# litefury5-final.net
KiCad netlist of a schematic drawn in EAGLE
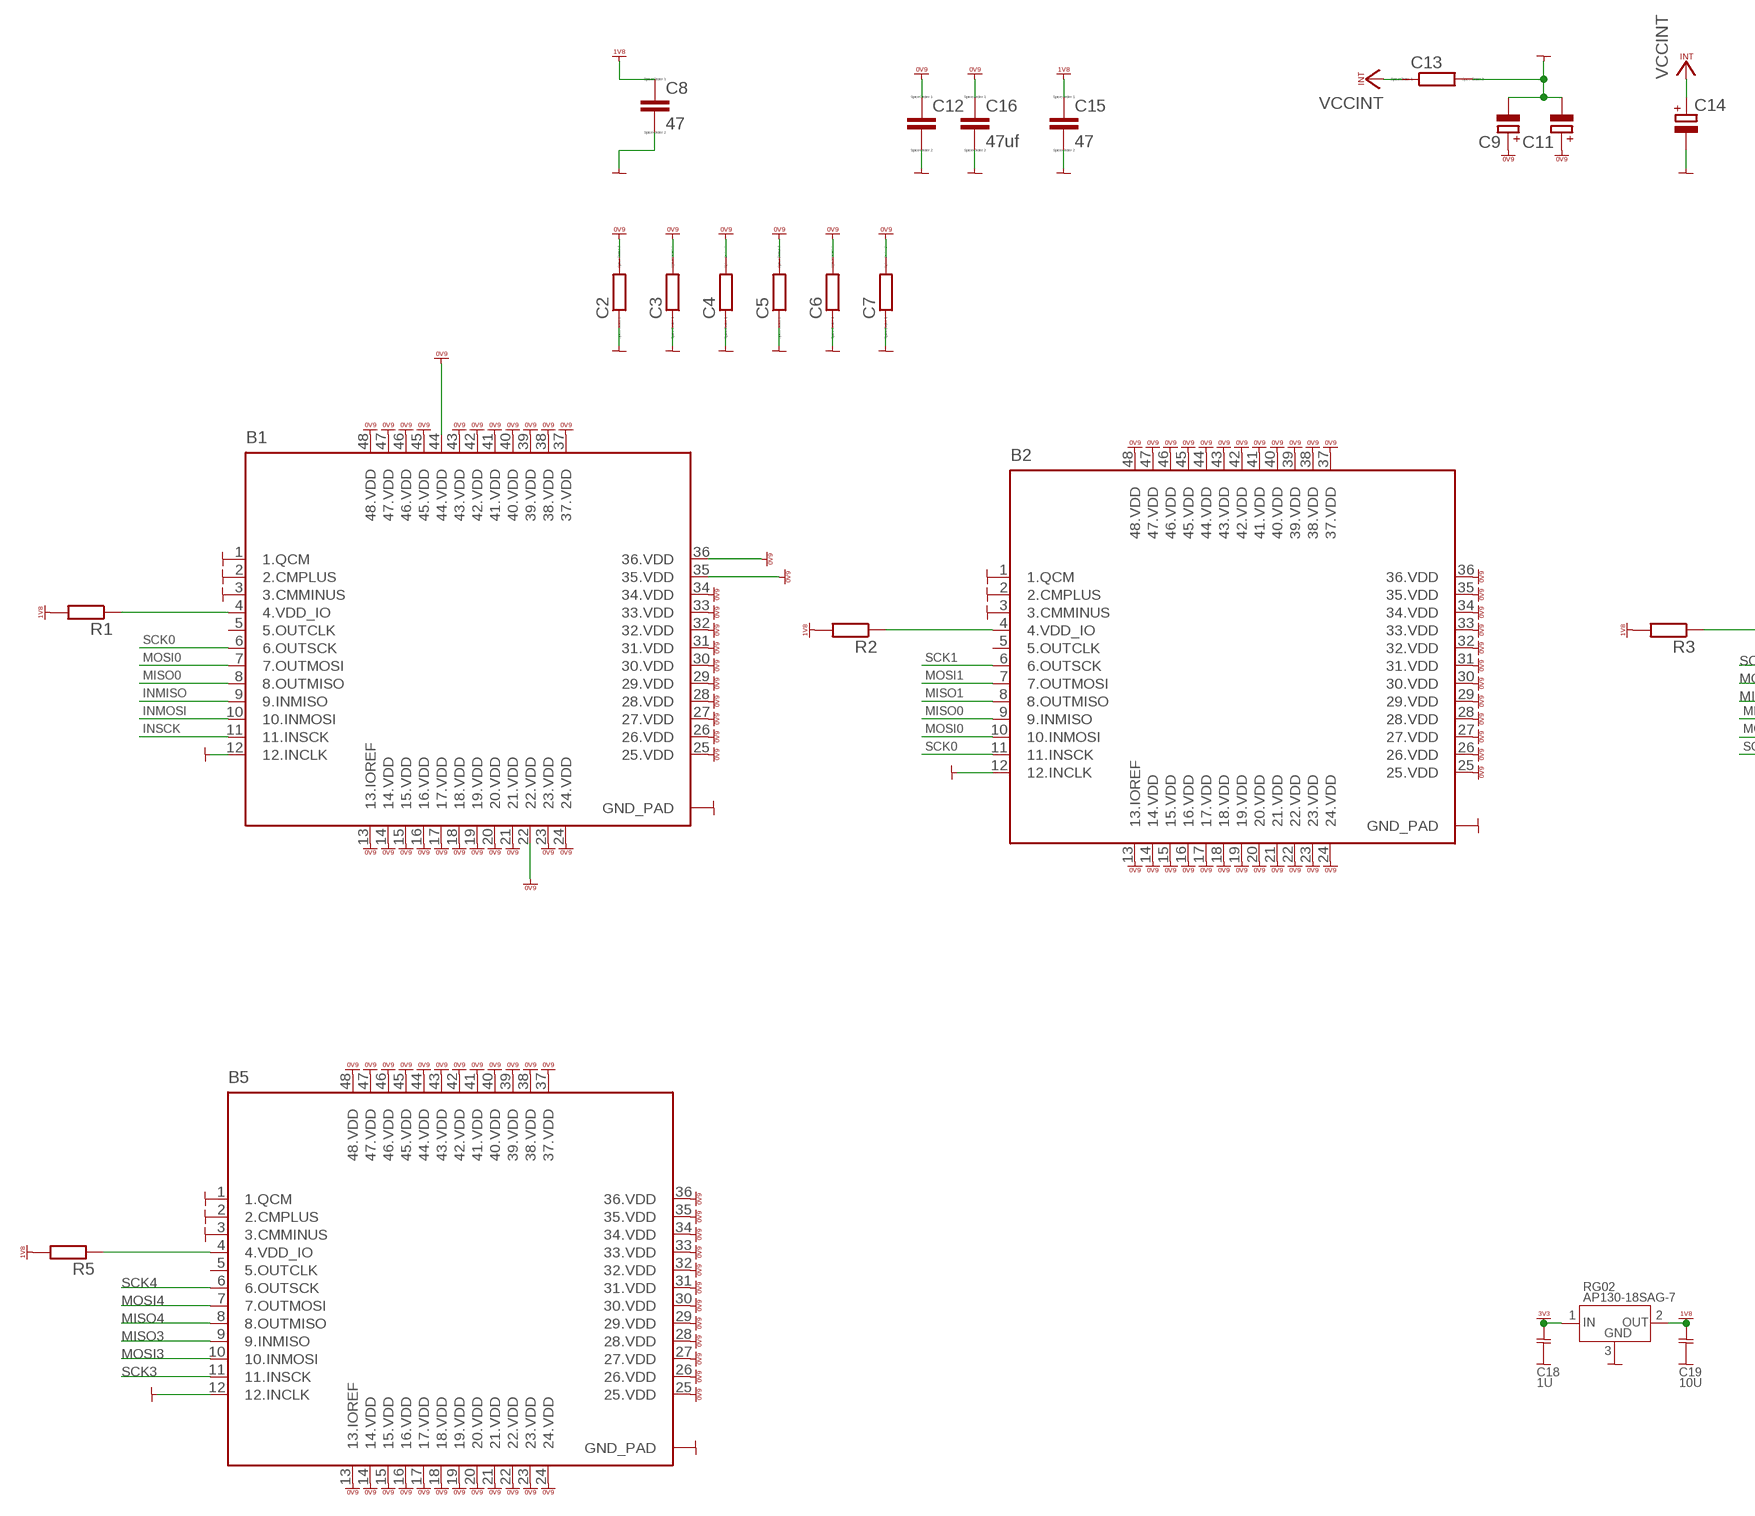
[diagram p0: schematic, sheet 1, part 1 of 2]
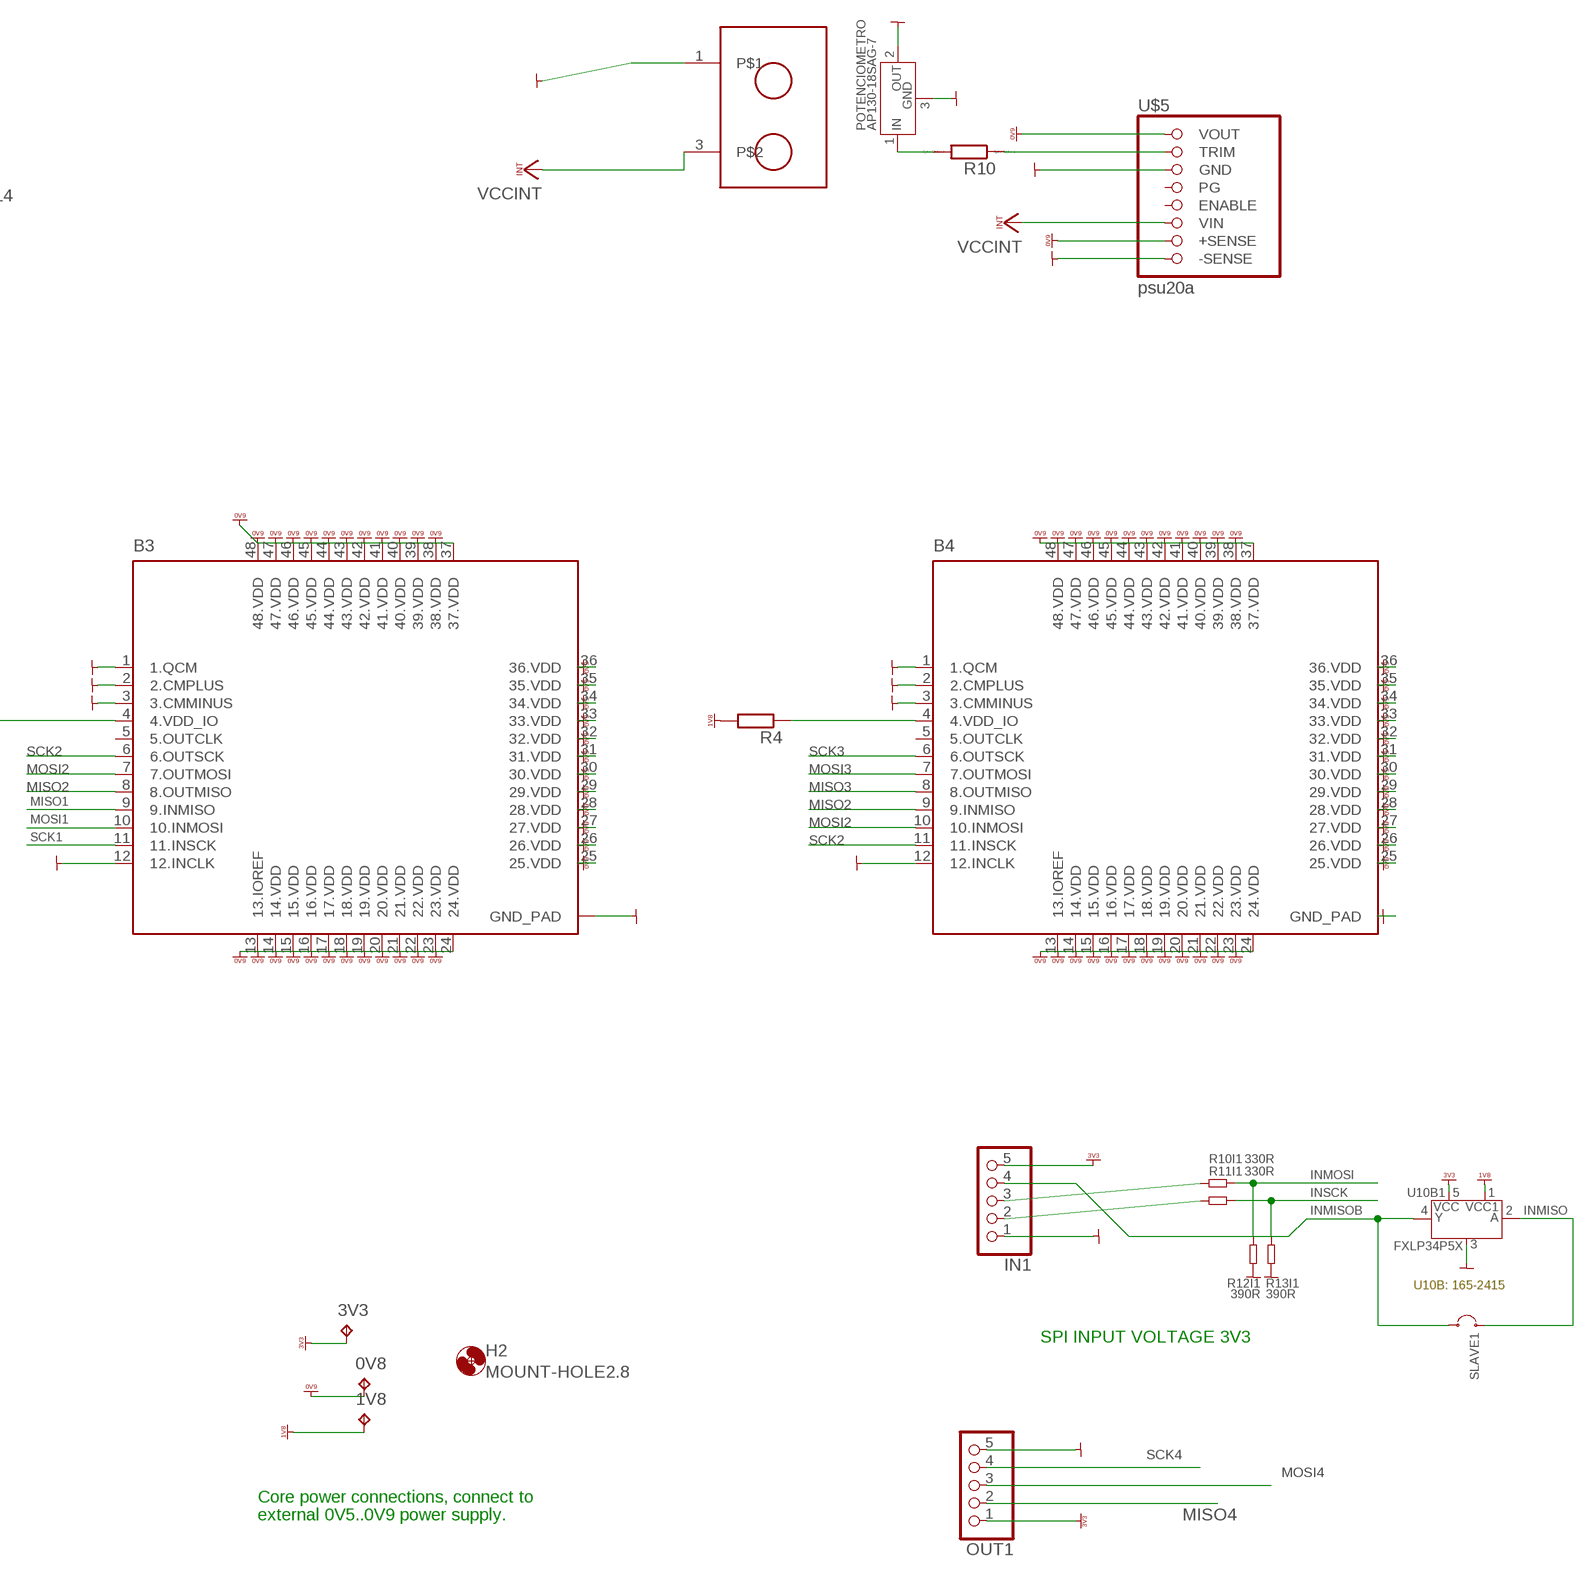
[diagram p1: schematic, sheet 1, part 2 of 2]

(export (version "E")
  (design (tool "Eeschema 10.0.6"))
  (components
    (comp (ref "0V8")
      (value "TPTP14SQ")
      (footprint "eagle-import:TP14SQ")
      (libsource (lib "eagle-import") (part "TPTP14SQ"))
    )
    (comp (ref "1V8")
      (value "TPTP10SQ")
      (footprint "eagle-import:TP10SQ")
      (libsource (lib "eagle-import") (part "TPTP10SQ"))
    )
    (comp (ref "3V3")
      (value "TPTP14SQ")
      (footprint "eagle-import:TP14SQ")
      (libsource (lib "eagle-import") (part "TPTP14SQ"))
    )
    (comp (ref "B1")
      (value "BITFURYM")
      (footprint "eagle-import:QFN48")
      (libsource (lib "eagle-import") (part "BITFURYM"))
    )
    (comp (ref "B2")
      (value "BITFURYM")
      (footprint "eagle-import:QFN48")
      (libsource (lib "eagle-import") (part "BITFURYM"))
    )
    (comp (ref "B3")
      (value "BITFURYM")
      (footprint "eagle-import:QFN48")
      (libsource (lib "eagle-import") (part "BITFURYM"))
    )
    (comp (ref "B4")
      (value "BITFURYM")
      (footprint "eagle-import:QFN48")
      (libsource (lib "eagle-import") (part "BITFURYM"))
    )
    (comp (ref "B5")
      (value "BITFURYM")
      (footprint "eagle-import:QFN48")
      (libsource (lib "eagle-import") (part "BITFURYM"))
    )
    (comp (ref "C2")
      (value "RR2010")
      (footprint "eagle-import:R2010")
      (libsource (lib "eagle-import") (part "RR2010"))
    )
    (comp (ref "C3")
      (value "RR2010")
      (footprint "eagle-import:R2010")
      (libsource (lib "eagle-import") (part "RR2010"))
    )
    (comp (ref "C4")
      (value "RR2010")
      (footprint "eagle-import:R2010")
      (libsource (lib "eagle-import") (part "RR2010"))
    )
    (comp (ref "C5")
      (value "RR2010")
      (footprint "eagle-import:R2010")
      (libsource (lib "eagle-import") (part "RR2010"))
    )
    (comp (ref "C6")
      (value "RR2010")
      (footprint "eagle-import:R2010")
      (libsource (lib "eagle-import") (part "RR2010"))
    )
    (comp (ref "C7")
      (value "RR2010")
      (footprint "eagle-import:R2010")
      (libsource (lib "eagle-import") (part "RR2010"))
    )
    (comp (ref "C8")
      (value "47")
      (footprint "eagle-import:C1210")
      (libsource (lib "eagle-import") (part "CC1210"))
    )
    (comp (ref "C9")
      (value "CPOL-EUCT7343")
      (footprint "eagle-import:CT7343")
      (libsource (lib "eagle-import") (part "CPOL-EUCT7343"))
    )
    (comp (ref "C11")
      (value "CPOL-EUCT7343")
      (footprint "eagle-import:CT7343")
      (libsource (lib "eagle-import") (part "CPOL-EUCT7343"))
    )
    (comp (ref "C12")
      (value "CC1210")
      (footprint "eagle-import:C1210")
      (libsource (lib "eagle-import") (part "CC1210"))
    )
    (comp (ref "C13")
      (value "RR2010")
      (footprint "eagle-import:R2010")
      (libsource (lib "eagle-import") (part "RR2010"))
    )
    (comp (ref "C14")
      (value "CPOL-EUCT7343")
      (footprint "eagle-import:CT7343")
      (libsource (lib "eagle-import") (part "CPOL-EUCT7343"))
    )
    (comp (ref "C15")
      (value "47")
      (footprint "eagle-import:C1210")
      (libsource (lib "eagle-import") (part "CC1210"))
    )
    (comp (ref "C16")
      (value "47uf")
      (footprint "eagle-import:C1210")
      (libsource (lib "eagle-import") (part "CC1210"))
    )
    (comp (ref "C18")
      (value "1U")
      (footprint "eagle-import:CAP0603")
      (libsource (lib "eagle-import") (part "CAP0603"))
    )
    (comp (ref "C19")
      (value "10U")
      (footprint "eagle-import:CAP0603")
      (libsource (lib "eagle-import") (part "CAP0603"))
    )
    (comp (ref "H2")
      (value "MOUNT-HOLE2.8")
      (footprint "eagle-import:2,8")
      (libsource (lib "eagle-import") (part "MOUNT-HOLE2.8"))
    )
    (comp (ref "IN1")
      (value "PINHD-1X5/90")
      (footprint "eagle-import:1X05_90")
      (libsource (lib "eagle-import") (part "PINHD-1X5/90"))
    )
    (comp (ref "OUT1")
      (value "PINHD-1X5/90")
      (footprint "eagle-import:1X05_90")
      (libsource (lib "eagle-import") (part "PINHD-1X5/90"))
    )
    (comp (ref "POTENCIOMETRO")
      (value "AP130-18SAG-7")
      (footprint "eagle-import:SOT23")
      (libsource (lib "eagle-import") (part "AP130-18SAG-7"))
    )
    (comp (ref "R1")
      (value "R-EU_R1206")
      (footprint "eagle-import:R1206")
      (libsource (lib "eagle-import") (part "R-EU_R1206"))
    )
    (comp (ref "R2")
      (value "R-EU_R1206")
      (footprint "eagle-import:R1206")
      (libsource (lib "eagle-import") (part "R-EU_R1206"))
    )
    (comp (ref "R3")
      (value "R-EU_R1206")
      (footprint "eagle-import:R1206")
      (libsource (lib "eagle-import") (part "R-EU_R1206"))
    )
    (comp (ref "R4")
      (value "R-EU_R1206")
      (footprint "eagle-import:R1206")
      (libsource (lib "eagle-import") (part "R-EU_R1206"))
    )
    (comp (ref "R5")
      (value "R-EU_R1206")
      (footprint "eagle-import:R1206")
      (libsource (lib "eagle-import") (part "R-EU_R1206"))
    )
    (comp (ref "R10")
      (value "RR0603")
      (footprint "eagle-import:R0603")
      (libsource (lib "eagle-import") (part "RR0603"))
    )
    (comp (ref "R10I1")
      (value "330R")
      (footprint "eagle-import:RES0603")
      (libsource (lib "eagle-import") (part "RES0603"))
    )
    (comp (ref "R11I1")
      (value "330R")
      (footprint "eagle-import:RES0603")
      (libsource (lib "eagle-import") (part "RES0603"))
    )
    (comp (ref "R12I1")
      (value "390R")
      (footprint "eagle-import:RES0603")
      (libsource (lib "eagle-import") (part "RES0603"))
    )
    (comp (ref "R13I1")
      (value "390R")
      (footprint "eagle-import:RES0603")
      (libsource (lib "eagle-import") (part "RES0603"))
    )
    (comp (ref "RG02")
      (value "AP130-18SAG-7")
      (footprint "eagle-import:SOT23")
      (libsource (lib "eagle-import") (part "AP130-18SAG-7"))
    )
    (comp (ref "SLAVE1")
      (value "SJ2SJ2-S")
      (footprint "eagle-import:SJ2-S")
      (libsource (lib "eagle-import") (part "SJ2SJ2-S"))
    )
    (comp (ref "U$5")
      (value "D12S05020")
      (footprint "eagle-import:PSU20A")
      (libsource (lib "eagle-import") (part "D12S05020"))
    )
    (comp (ref "U$6")
      (value "RTORNILLO")
      (footprint "eagle-import:REGLETATORNILLO")
      (libsource (lib "eagle-import") (part "RTORNILLO"))
    )
    (comp (ref "U10B1")
      (value "FXLP34P5X")
      (footprint "eagle-import:SOT23-5")
      (libsource (lib "eagle-import") (part "FXLP34P5X"))
    )
  )
  (nets
    (net (code "1") (name "/INMISO") (class "Default")
      (node (ref "B1") (pin "9") (pinfunction "9.INMISO_9") (pintype "bidirectional"))
      (node (ref "SLAVE1") (pin "2") (pinfunction "P$2_2") (pintype "passive"))
      (node (ref "U10B1") (pin "2") (pinfunction "2.A_2") (pintype "passive"))
    )
    (net (code "2") (name "/INMISOB") (class "Default")
      (node (ref "IN1") (pin "4") (pinfunction "4_4") (pintype "passive"))
      (node (ref "SLAVE1") (pin "1") (pinfunction "P$1_1") (pintype "passive"))
      (node (ref "U10B1") (pin "4") (pinfunction "4.Y_4") (pintype "passive"))
    )
    (net (code "3") (name "/INMOSI") (class "Default")
      (node (ref "B1") (pin "10") (pinfunction "10.INMOSI_10") (pintype "bidirectional"))
      (node (ref "R10I1") (pin "2") (pinfunction "2_2") (pintype "passive"))
      (node (ref "R12I1") (pin "2") (pinfunction "2_2") (pintype "passive"))
    )
    (net (code "4") (name "/INSCK") (class "Default")
      (node (ref "B1") (pin "11") (pinfunction "11.INSCK_11") (pintype "bidirectional"))
      (node (ref "R11I1") (pin "2") (pinfunction "2_2") (pintype "passive"))
      (node (ref "R13I1") (pin "2") (pinfunction "2_2") (pintype "passive"))
    )
    (net (code "5") (name "/MISO0") (class "Default")
      (node (ref "B1") (pin "8") (pinfunction "8.OUTMISO_8") (pintype "bidirectional"))
      (node (ref "B2") (pin "9") (pinfunction "9.INMISO_9") (pintype "bidirectional"))
    )
    (net (code "6") (name "/MISO1") (class "Default")
      (node (ref "B2") (pin "8") (pinfunction "8.OUTMISO_8") (pintype "bidirectional"))
      (node (ref "B3") (pin "9") (pinfunction "9.INMISO_9") (pintype "bidirectional"))
    )
    (net (code "7") (name "/MISO2") (class "Default")
      (node (ref "B3") (pin "8") (pinfunction "8.OUTMISO_8") (pintype "bidirectional"))
      (node (ref "B4") (pin "9") (pinfunction "9.INMISO_9") (pintype "bidirectional"))
    )
    (net (code "8") (name "/MISO3") (class "Default")
      (node (ref "B4") (pin "8") (pinfunction "8.OUTMISO_8") (pintype "bidirectional"))
      (node (ref "B5") (pin "9") (pinfunction "9.INMISO_9") (pintype "bidirectional"))
    )
    (net (code "9") (name "/MISO4") (class "Default")
      (node (ref "B5") (pin "8") (pinfunction "8.OUTMISO_8") (pintype "bidirectional"))
      (node (ref "OUT1") (pin "2") (pinfunction "2_2") (pintype "passive"))
    )
    (net (code "10") (name "/MOSI0") (class "Default")
      (node (ref "B1") (pin "7") (pinfunction "7.OUTMOSI_7") (pintype "bidirectional"))
      (node (ref "B2") (pin "10") (pinfunction "10.INMOSI_10") (pintype "bidirectional"))
    )
    (net (code "11") (name "/MOSI1") (class "Default")
      (node (ref "B2") (pin "7") (pinfunction "7.OUTMOSI_7") (pintype "bidirectional"))
      (node (ref "B3") (pin "10") (pinfunction "10.INMOSI_10") (pintype "bidirectional"))
    )
    (net (code "12") (name "/MOSI2") (class "Default")
      (node (ref "B3") (pin "7") (pinfunction "7.OUTMOSI_7") (pintype "bidirectional"))
      (node (ref "B4") (pin "10") (pinfunction "10.INMOSI_10") (pintype "bidirectional"))
    )
    (net (code "13") (name "/MOSI3") (class "Default")
      (node (ref "B4") (pin "7") (pinfunction "7.OUTMOSI_7") (pintype "bidirectional"))
      (node (ref "B5") (pin "10") (pinfunction "10.INMOSI_10") (pintype "bidirectional"))
    )
    (net (code "14") (name "/MOSI4") (class "Default")
      (node (ref "B5") (pin "7") (pinfunction "7.OUTMOSI_7") (pintype "bidirectional"))
      (node (ref "OUT1") (pin "3") (pinfunction "3_3") (pintype "passive"))
    )
    (net (code "15") (name "/SCK0") (class "Default")
      (node (ref "B1") (pin "6") (pinfunction "6.OUTSCK_6") (pintype "bidirectional"))
      (node (ref "B2") (pin "11") (pinfunction "11.INSCK_11") (pintype "bidirectional"))
    )
    (net (code "16") (name "/SCK1") (class "Default")
      (node (ref "B2") (pin "6") (pinfunction "6.OUTSCK_6") (pintype "bidirectional"))
      (node (ref "B3") (pin "11") (pinfunction "11.INSCK_11") (pintype "bidirectional"))
    )
    (net (code "17") (name "/SCK2") (class "Default")
      (node (ref "B3") (pin "6") (pinfunction "6.OUTSCK_6") (pintype "bidirectional"))
      (node (ref "B4") (pin "11") (pinfunction "11.INSCK_11") (pintype "bidirectional"))
    )
    (net (code "18") (name "/SCK3") (class "Default")
      (node (ref "B4") (pin "6") (pinfunction "6.OUTSCK_6") (pintype "bidirectional"))
      (node (ref "B5") (pin "11") (pinfunction "11.INSCK_11") (pintype "bidirectional"))
    )
    (net (code "19") (name "/SCK4") (class "Default")
      (node (ref "B5") (pin "6") (pinfunction "6.OUTSCK_6") (pintype "bidirectional"))
      (node (ref "OUT1") (pin "4") (pinfunction "4_4") (pintype "passive"))
    )
    (net (code "20") (name "GND") (class "Default")
      (node (ref "B1") (pin "1") (pinfunction "1.QCM_1") (pintype "bidirectional"))
      (node (ref "B1") (pin "12") (pinfunction "12.INCLK_12") (pintype "bidirectional"))
      (node (ref "B1") (pin "2") (pinfunction "2.CMPLUS_2") (pintype "bidirectional"))
      (node (ref "B1") (pin "3") (pinfunction "3.CMMINUS_3") (pintype "bidirectional"))
      (node (ref "B1") (pin "EXP") (pinfunction "GND_PAD_EXP") (pintype "bidirectional"))
      (node (ref "B1") (pin "P$1") (pinfunction "GND_PAD_P$1") (pintype "bidirectional"))
      (node (ref "B1") (pin "P$10") (pinfunction "GND_PAD_P$10") (pintype "bidirectional"))
      (node (ref "B1") (pin "P$11") (pinfunction "GND_PAD_P$11") (pintype "bidirectional"))
      (node (ref "B1") (pin "P$12") (pinfunction "GND_PAD_P$12") (pintype "bidirectional"))
      (node (ref "B1") (pin "P$13") (pinfunction "GND_PAD_P$13") (pintype "bidirectional"))
      (node (ref "B1") (pin "P$14") (pinfunction "GND_PAD_P$14") (pintype "bidirectional"))
      (node (ref "B1") (pin "P$15") (pinfunction "GND_PAD_P$15") (pintype "bidirectional"))
      (node (ref "B1") (pin "P$16") (pinfunction "GND_PAD_P$16") (pintype "bidirectional"))
      (node (ref "B1") (pin "P$17") (pinfunction "GND_PAD_P$17") (pintype "bidirectional"))
      (node (ref "B1") (pin "P$18") (pinfunction "GND_PAD_P$18") (pintype "bidirectional"))
      (node (ref "B1") (pin "P$19") (pinfunction "GND_PAD_P$19") (pintype "bidirectional"))
      (node (ref "B1") (pin "P$2") (pinfunction "GND_PAD_P$2") (pintype "bidirectional"))
      (node (ref "B1") (pin "P$20") (pinfunction "GND_PAD_P$20") (pintype "bidirectional"))
      (node (ref "B1") (pin "P$21") (pinfunction "GND_PAD_P$21") (pintype "bidirectional"))
      (node (ref "B1") (pin "P$22") (pinfunction "GND_PAD_P$22") (pintype "bidirectional"))
      (node (ref "B1") (pin "P$23") (pinfunction "GND_PAD_P$23") (pintype "bidirectional"))
      (node (ref "B1") (pin "P$24") (pinfunction "GND_PAD_P$24") (pintype "bidirectional"))
      (node (ref "B1") (pin "P$25") (pinfunction "GND_PAD_P$25") (pintype "bidirectional"))
      (node (ref "B1") (pin "P$3") (pinfunction "GND_PAD_P$3") (pintype "bidirectional"))
      (node (ref "B1") (pin "P$4") (pinfunction "GND_PAD_P$4") (pintype "bidirectional"))
      (node (ref "B1") (pin "P$5") (pinfunction "GND_PAD_P$5") (pintype "bidirectional"))
      (node (ref "B1") (pin "P$6") (pinfunction "GND_PAD_P$6") (pintype "bidirectional"))
      (node (ref "B1") (pin "P$7") (pinfunction "GND_PAD_P$7") (pintype "bidirectional"))
      (node (ref "B1") (pin "P$8") (pinfunction "GND_PAD_P$8") (pintype "bidirectional"))
      (node (ref "B1") (pin "P$9") (pinfunction "GND_PAD_P$9") (pintype "bidirectional"))
      (node (ref "B2") (pin "1") (pinfunction "1.QCM_1") (pintype "bidirectional"))
      (node (ref "B2") (pin "12") (pinfunction "12.INCLK_12") (pintype "bidirectional"))
      (node (ref "B2") (pin "2") (pinfunction "2.CMPLUS_2") (pintype "bidirectional"))
      (node (ref "B2") (pin "3") (pinfunction "3.CMMINUS_3") (pintype "bidirectional"))
      (node (ref "B2") (pin "EXP") (pinfunction "GND_PAD_EXP") (pintype "bidirectional"))
      (node (ref "B2") (pin "P$1") (pinfunction "GND_PAD_P$1") (pintype "bidirectional"))
      (node (ref "B2") (pin "P$10") (pinfunction "GND_PAD_P$10") (pintype "bidirectional"))
      (node (ref "B2") (pin "P$11") (pinfunction "GND_PAD_P$11") (pintype "bidirectional"))
      (node (ref "B2") (pin "P$12") (pinfunction "GND_PAD_P$12") (pintype "bidirectional"))
      (node (ref "B2") (pin "P$13") (pinfunction "GND_PAD_P$13") (pintype "bidirectional"))
      (node (ref "B2") (pin "P$14") (pinfunction "GND_PAD_P$14") (pintype "bidirectional"))
      (node (ref "B2") (pin "P$15") (pinfunction "GND_PAD_P$15") (pintype "bidirectional"))
      (node (ref "B2") (pin "P$16") (pinfunction "GND_PAD_P$16") (pintype "bidirectional"))
      (node (ref "B2") (pin "P$17") (pinfunction "GND_PAD_P$17") (pintype "bidirectional"))
      (node (ref "B2") (pin "P$18") (pinfunction "GND_PAD_P$18") (pintype "bidirectional"))
      (node (ref "B2") (pin "P$19") (pinfunction "GND_PAD_P$19") (pintype "bidirectional"))
      (node (ref "B2") (pin "P$2") (pinfunction "GND_PAD_P$2") (pintype "bidirectional"))
      (node (ref "B2") (pin "P$20") (pinfunction "GND_PAD_P$20") (pintype "bidirectional"))
      (node (ref "B2") (pin "P$21") (pinfunction "GND_PAD_P$21") (pintype "bidirectional"))
      (node (ref "B2") (pin "P$22") (pinfunction "GND_PAD_P$22") (pintype "bidirectional"))
      (node (ref "B2") (pin "P$23") (pinfunction "GND_PAD_P$23") (pintype "bidirectional"))
      (node (ref "B2") (pin "P$24") (pinfunction "GND_PAD_P$24") (pintype "bidirectional"))
      (node (ref "B2") (pin "P$25") (pinfunction "GND_PAD_P$25") (pintype "bidirectional"))
      (node (ref "B2") (pin "P$3") (pinfunction "GND_PAD_P$3") (pintype "bidirectional"))
      (node (ref "B2") (pin "P$4") (pinfunction "GND_PAD_P$4") (pintype "bidirectional"))
      (node (ref "B2") (pin "P$5") (pinfunction "GND_PAD_P$5") (pintype "bidirectional"))
      (node (ref "B2") (pin "P$6") (pinfunction "GND_PAD_P$6") (pintype "bidirectional"))
      (node (ref "B2") (pin "P$7") (pinfunction "GND_PAD_P$7") (pintype "bidirectional"))
      (node (ref "B2") (pin "P$8") (pinfunction "GND_PAD_P$8") (pintype "bidirectional"))
      (node (ref "B2") (pin "P$9") (pinfunction "GND_PAD_P$9") (pintype "bidirectional"))
      (node (ref "B3") (pin "1") (pinfunction "1.QCM_1") (pintype "bidirectional"))
      (node (ref "B3") (pin "12") (pinfunction "12.INCLK_12") (pintype "bidirectional"))
      (node (ref "B3") (pin "2") (pinfunction "2.CMPLUS_2") (pintype "bidirectional"))
      (node (ref "B3") (pin "3") (pinfunction "3.CMMINUS_3") (pintype "bidirectional"))
      (node (ref "B3") (pin "EXP") (pinfunction "GND_PAD_EXP") (pintype "bidirectional"))
      (node (ref "B3") (pin "P$1") (pinfunction "GND_PAD_P$1") (pintype "bidirectional"))
      (node (ref "B3") (pin "P$10") (pinfunction "GND_PAD_P$10") (pintype "bidirectional"))
      (node (ref "B3") (pin "P$11") (pinfunction "GND_PAD_P$11") (pintype "bidirectional"))
      (node (ref "B3") (pin "P$12") (pinfunction "GND_PAD_P$12") (pintype "bidirectional"))
      (node (ref "B3") (pin "P$13") (pinfunction "GND_PAD_P$13") (pintype "bidirectional"))
      (node (ref "B3") (pin "P$14") (pinfunction "GND_PAD_P$14") (pintype "bidirectional"))
      (node (ref "B3") (pin "P$15") (pinfunction "GND_PAD_P$15") (pintype "bidirectional"))
      (node (ref "B3") (pin "P$16") (pinfunction "GND_PAD_P$16") (pintype "bidirectional"))
      (node (ref "B3") (pin "P$17") (pinfunction "GND_PAD_P$17") (pintype "bidirectional"))
      (node (ref "B3") (pin "P$18") (pinfunction "GND_PAD_P$18") (pintype "bidirectional"))
      (node (ref "B3") (pin "P$19") (pinfunction "GND_PAD_P$19") (pintype "bidirectional"))
      (node (ref "B3") (pin "P$2") (pinfunction "GND_PAD_P$2") (pintype "bidirectional"))
      (node (ref "B3") (pin "P$20") (pinfunction "GND_PAD_P$20") (pintype "bidirectional"))
      (node (ref "B3") (pin "P$21") (pinfunction "GND_PAD_P$21") (pintype "bidirectional"))
      (node (ref "B3") (pin "P$22") (pinfunction "GND_PAD_P$22") (pintype "bidirectional"))
      (node (ref "B3") (pin "P$23") (pinfunction "GND_PAD_P$23") (pintype "bidirectional"))
      (node (ref "B3") (pin "P$24") (pinfunction "GND_PAD_P$24") (pintype "bidirectional"))
      (node (ref "B3") (pin "P$25") (pinfunction "GND_PAD_P$25") (pintype "bidirectional"))
      (node (ref "B3") (pin "P$3") (pinfunction "GND_PAD_P$3") (pintype "bidirectional"))
      (node (ref "B3") (pin "P$4") (pinfunction "GND_PAD_P$4") (pintype "bidirectional"))
      (node (ref "B3") (pin "P$5") (pinfunction "GND_PAD_P$5") (pintype "bidirectional"))
      (node (ref "B3") (pin "P$6") (pinfunction "GND_PAD_P$6") (pintype "bidirectional"))
      (node (ref "B3") (pin "P$7") (pinfunction "GND_PAD_P$7") (pintype "bidirectional"))
      (node (ref "B3") (pin "P$8") (pinfunction "GND_PAD_P$8") (pintype "bidirectional"))
      (node (ref "B3") (pin "P$9") (pinfunction "GND_PAD_P$9") (pintype "bidirectional"))
      (node (ref "B4") (pin "1") (pinfunction "1.QCM_1") (pintype "bidirectional"))
      (node (ref "B4") (pin "12") (pinfunction "12.INCLK_12") (pintype "bidirectional"))
      (node (ref "B4") (pin "2") (pinfunction "2.CMPLUS_2") (pintype "bidirectional"))
      (node (ref "B4") (pin "3") (pinfunction "3.CMMINUS_3") (pintype "bidirectional"))
      (node (ref "B4") (pin "EXP") (pinfunction "GND_PAD_EXP") (pintype "bidirectional"))
      (node (ref "B4") (pin "P$1") (pinfunction "GND_PAD_P$1") (pintype "bidirectional"))
      (node (ref "B4") (pin "P$10") (pinfunction "GND_PAD_P$10") (pintype "bidirectional"))
      (node (ref "B4") (pin "P$11") (pinfunction "GND_PAD_P$11") (pintype "bidirectional"))
      (node (ref "B4") (pin "P$12") (pinfunction "GND_PAD_P$12") (pintype "bidirectional"))
      (node (ref "B4") (pin "P$13") (pinfunction "GND_PAD_P$13") (pintype "bidirectional"))
      (node (ref "B4") (pin "P$14") (pinfunction "GND_PAD_P$14") (pintype "bidirectional"))
      (node (ref "B4") (pin "P$15") (pinfunction "GND_PAD_P$15") (pintype "bidirectional"))
      (node (ref "B4") (pin "P$16") (pinfunction "GND_PAD_P$16") (pintype "bidirectional"))
      (node (ref "B4") (pin "P$17") (pinfunction "GND_PAD_P$17") (pintype "bidirectional"))
      (node (ref "B4") (pin "P$18") (pinfunction "GND_PAD_P$18") (pintype "bidirectional"))
      (node (ref "B4") (pin "P$19") (pinfunction "GND_PAD_P$19") (pintype "bidirectional"))
      (node (ref "B4") (pin "P$2") (pinfunction "GND_PAD_P$2") (pintype "bidirectional"))
      (node (ref "B4") (pin "P$20") (pinfunction "GND_PAD_P$20") (pintype "bidirectional"))
      (node (ref "B4") (pin "P$21") (pinfunction "GND_PAD_P$21") (pintype "bidirectional"))
      (node (ref "B4") (pin "P$22") (pinfunction "GND_PAD_P$22") (pintype "bidirectional"))
      (node (ref "B4") (pin "P$23") (pinfunction "GND_PAD_P$23") (pintype "bidirectional"))
      (node (ref "B4") (pin "P$24") (pinfunction "GND_PAD_P$24") (pintype "bidirectional"))
      (node (ref "B4") (pin "P$25") (pinfunction "GND_PAD_P$25") (pintype "bidirectional"))
      (node (ref "B4") (pin "P$3") (pinfunction "GND_PAD_P$3") (pintype "bidirectional"))
      (node (ref "B4") (pin "P$4") (pinfunction "GND_PAD_P$4") (pintype "bidirectional"))
      (node (ref "B4") (pin "P$5") (pinfunction "GND_PAD_P$5") (pintype "bidirectional"))
      (node (ref "B4") (pin "P$6") (pinfunction "GND_PAD_P$6") (pintype "bidirectional"))
      (node (ref "B4") (pin "P$7") (pinfunction "GND_PAD_P$7") (pintype "bidirectional"))
      (node (ref "B4") (pin "P$8") (pinfunction "GND_PAD_P$8") (pintype "bidirectional"))
      (node (ref "B4") (pin "P$9") (pinfunction "GND_PAD_P$9") (pintype "bidirectional"))
      (node (ref "B5") (pin "1") (pinfunction "1.QCM_1") (pintype "bidirectional"))
      (node (ref "B5") (pin "12") (pinfunction "12.INCLK_12") (pintype "bidirectional"))
      (node (ref "B5") (pin "2") (pinfunction "2.CMPLUS_2") (pintype "bidirectional"))
      (node (ref "B5") (pin "3") (pinfunction "3.CMMINUS_3") (pintype "bidirectional"))
      (node (ref "B5") (pin "EXP") (pinfunction "GND_PAD_EXP") (pintype "bidirectional"))
      (node (ref "B5") (pin "P$1") (pinfunction "GND_PAD_P$1") (pintype "bidirectional"))
      (node (ref "B5") (pin "P$10") (pinfunction "GND_PAD_P$10") (pintype "bidirectional"))
      (node (ref "B5") (pin "P$11") (pinfunction "GND_PAD_P$11") (pintype "bidirectional"))
      (node (ref "B5") (pin "P$12") (pinfunction "GND_PAD_P$12") (pintype "bidirectional"))
      (node (ref "B5") (pin "P$13") (pinfunction "GND_PAD_P$13") (pintype "bidirectional"))
      (node (ref "B5") (pin "P$14") (pinfunction "GND_PAD_P$14") (pintype "bidirectional"))
      (node (ref "B5") (pin "P$15") (pinfunction "GND_PAD_P$15") (pintype "bidirectional"))
      (node (ref "B5") (pin "P$16") (pinfunction "GND_PAD_P$16") (pintype "bidirectional"))
      (node (ref "B5") (pin "P$17") (pinfunction "GND_PAD_P$17") (pintype "bidirectional"))
      (node (ref "B5") (pin "P$18") (pinfunction "GND_PAD_P$18") (pintype "bidirectional"))
      (node (ref "B5") (pin "P$19") (pinfunction "GND_PAD_P$19") (pintype "bidirectional"))
      (node (ref "B5") (pin "P$2") (pinfunction "GND_PAD_P$2") (pintype "bidirectional"))
      (node (ref "B5") (pin "P$20") (pinfunction "GND_PAD_P$20") (pintype "bidirectional"))
      (node (ref "B5") (pin "P$21") (pinfunction "GND_PAD_P$21") (pintype "bidirectional"))
      (node (ref "B5") (pin "P$22") (pinfunction "GND_PAD_P$22") (pintype "bidirectional"))
      (node (ref "B5") (pin "P$23") (pinfunction "GND_PAD_P$23") (pintype "bidirectional"))
      (node (ref "B5") (pin "P$24") (pinfunction "GND_PAD_P$24") (pintype "bidirectional"))
      (node (ref "B5") (pin "P$25") (pinfunction "GND_PAD_P$25") (pintype "bidirectional"))
      (node (ref "B5") (pin "P$3") (pinfunction "GND_PAD_P$3") (pintype "bidirectional"))
      (node (ref "B5") (pin "P$4") (pinfunction "GND_PAD_P$4") (pintype "bidirectional"))
      (node (ref "B5") (pin "P$5") (pinfunction "GND_PAD_P$5") (pintype "bidirectional"))
      (node (ref "B5") (pin "P$6") (pinfunction "GND_PAD_P$6") (pintype "bidirectional"))
      (node (ref "B5") (pin "P$7") (pinfunction "GND_PAD_P$7") (pintype "bidirectional"))
      (node (ref "B5") (pin "P$8") (pinfunction "GND_PAD_P$8") (pintype "bidirectional"))
      (node (ref "B5") (pin "P$9") (pinfunction "GND_PAD_P$9") (pintype "bidirectional"))
      (node (ref "C11") (pin "-") (pinfunction "-_-") (pintype "passive"))
      (node (ref "C12") (pin "2") (pinfunction "2_2") (pintype "passive"))
      (node (ref "C13") (pin "2") (pinfunction "2_2") (pintype "passive"))
      (node (ref "C14") (pin "-") (pinfunction "-_-") (pintype "passive"))
      (node (ref "C15") (pin "2") (pinfunction "2_2") (pintype "passive"))
      (node (ref "C16") (pin "2") (pinfunction "2_2") (pintype "passive"))
      (node (ref "C18") (pin "2") (pinfunction "2_2") (pintype "passive"))
      (node (ref "C19") (pin "2") (pinfunction "2_2") (pintype "passive"))
      (node (ref "C2") (pin "1") (pinfunction "1_1") (pintype "passive"))
      (node (ref "C3") (pin "1") (pinfunction "1_1") (pintype "passive"))
      (node (ref "C4") (pin "1") (pinfunction "1_1") (pintype "passive"))
      (node (ref "C5") (pin "1") (pinfunction "1_1") (pintype "passive"))
      (node (ref "C6") (pin "1") (pinfunction "1_1") (pintype "passive"))
      (node (ref "C7") (pin "1") (pinfunction "1_1") (pintype "passive"))
      (node (ref "C8") (pin "2") (pinfunction "2_2") (pintype "passive"))
      (node (ref "C9") (pin "-") (pinfunction "-_-") (pintype "passive"))
      (node (ref "IN1") (pin "1") (pinfunction "1_1") (pintype "passive"))
      (node (ref "OUT1") (pin "5") (pinfunction "5_5") (pintype "passive"))
      (node (ref "POTENCIOMETRO") (pin "2") (pinfunction "2.OUT_2") (pintype "passive"))
      (node (ref "POTENCIOMETRO") (pin "3") (pinfunction "3.GND_3") (pintype "passive"))
      (node (ref "R12I1") (pin "1") (pinfunction "1_1") (pintype "passive"))
      (node (ref "R13I1") (pin "1") (pinfunction "1_1") (pintype "passive"))
      (node (ref "RG02") (pin "3") (pinfunction "3.GND_3") (pintype "passive"))
      (node (ref "U$5") (pin "3") (pinfunction "GND_3") (pintype "passive"))
      (node (ref "U$5") (pin "8") (pinfunction "-SENSE_8") (pintype "passive"))
      (node (ref "U$6") (pin "1") (pinfunction "P$1_1") (pintype "bidirectional"))
      (node (ref "U10B1") (pin "3") (pinfunction "3.GND_3") (pintype "passive"))
    )
    (net (code "21") (name "Net-(B1-4.VDD_IO)") (class "Default")
      (node (ref "B1") (pin "4") (pinfunction "4.VDD_IO_4") (pintype "bidirectional"))
      (node (ref "R1") (pin "1") (pinfunction "1_1") (pintype "passive"))
    )
    (net (code "22") (name "Net-(B2-4.VDD_IO)") (class "Default")
      (node (ref "B2") (pin "4") (pinfunction "4.VDD_IO_4") (pintype "bidirectional"))
      (node (ref "R2") (pin "1") (pinfunction "1_1") (pintype "passive"))
    )
    (net (code "23") (name "Net-(B3-4.VDD_IO)") (class "Default")
      (node (ref "B3") (pin "4") (pinfunction "4.VDD_IO_4") (pintype "bidirectional"))
      (node (ref "R3") (pin "1") (pinfunction "1_1") (pintype "passive"))
    )
    (net (code "24") (name "Net-(B4-4.VDD_IO)") (class "Default")
      (node (ref "B4") (pin "4") (pinfunction "4.VDD_IO_4") (pintype "bidirectional"))
      (node (ref "R4") (pin "1") (pinfunction "1_1") (pintype "passive"))
    )
    (net (code "25") (name "Net-(B5-4.VDD_IO)") (class "Default")
      (node (ref "B5") (pin "4") (pinfunction "4.VDD_IO_4") (pintype "bidirectional"))
      (node (ref "R5") (pin "1") (pinfunction "1_1") (pintype "passive"))
    )
    (net (code "26") (name "Net-(IN1-Pad2)") (class "Default")
      (node (ref "IN1") (pin "2") (pinfunction "2_2") (pintype "passive"))
      (node (ref "R11I1") (pin "1") (pinfunction "1_1") (pintype "passive"))
    )
    (net (code "27") (name "Net-(IN1-Pad3)") (class "Default")
      (node (ref "IN1") (pin "3") (pinfunction "3_3") (pintype "passive"))
      (node (ref "R10I1") (pin "1") (pinfunction "1_1") (pintype "passive"))
    )
    (net (code "28") (name "Net-(POTENCIOMETRO-1.IN)") (class "Default")
      (node (ref "POTENCIOMETRO") (pin "1") (pinfunction "1.IN_1") (pintype "passive"))
      (node (ref "R10") (pin "2") (pinfunction "2_2") (pintype "passive"))
    )
    (net (code "29") (name "Net-(U$5-TRIM)") (class "Default")
      (node (ref "R10") (pin "1") (pinfunction "1_1") (pintype "passive"))
      (node (ref "U$5") (pin "2") (pinfunction "TRIM_2") (pintype "passive"))
    )
    (net (code "30") (name "VCCINT") (class "Default")
      (node (ref "C13") (pin "1") (pinfunction "1_1") (pintype "passive"))
      (node (ref "C14") (pin "+") (pinfunction "+_+") (pintype "passive"))
      (node (ref "U$5") (pin "6") (pinfunction "VIN_6") (pintype "passive"))
      (node (ref "U$6") (pin "3") (pinfunction "P$2_3") (pintype "bidirectional"))
    )
    (net (code "31") (name "VCC_0V9") (class "Default")
      (node (ref "0V8") (pin "TP") (pinfunction "TP_TP") (pintype "input"))
      (node (ref "B1") (pin "13") (pinfunction "13.IOREF_13") (pintype "bidirectional"))
      (node (ref "B1") (pin "14") (pinfunction "14.VDD_14") (pintype "bidirectional"))
      (node (ref "B1") (pin "15") (pinfunction "15.VDD_15") (pintype "bidirectional"))
      (node (ref "B1") (pin "16") (pinfunction "16.VDD_16") (pintype "bidirectional"))
      (node (ref "B1") (pin "17") (pinfunction "17.VDD_17") (pintype "power_in"))
      (node (ref "B1") (pin "18") (pinfunction "18.VDD_18") (pintype "power_in"))
      (node (ref "B1") (pin "19") (pinfunction "19.VDD_19") (pintype "power_in"))
      (node (ref "B1") (pin "20") (pinfunction "20.VDD_20") (pintype "bidirectional"))
      (node (ref "B1") (pin "21") (pinfunction "21.VDD_21") (pintype "bidirectional"))
      (node (ref "B1") (pin "22") (pinfunction "22.VDD_22") (pintype "bidirectional"))
      (node (ref "B1") (pin "23") (pinfunction "23.VDD_23") (pintype "bidirectional"))
      (node (ref "B1") (pin "24") (pinfunction "24.VDD_24") (pintype "bidirectional"))
      (node (ref "B1") (pin "25") (pinfunction "25.VDD_25") (pintype "bidirectional"))
      (node (ref "B1") (pin "26") (pinfunction "26.VDD_26") (pintype "bidirectional"))
      (node (ref "B1") (pin "27") (pinfunction "27.VDD_27") (pintype "bidirectional"))
      (node (ref "B1") (pin "28") (pinfunction "28.VDD_28") (pintype "bidirectional"))
      (node (ref "B1") (pin "29") (pinfunction "29.VDD_29") (pintype "bidirectional"))
      (node (ref "B1") (pin "30") (pinfunction "30.VDD_30") (pintype "bidirectional"))
      (node (ref "B1") (pin "31") (pinfunction "31.VDD_31") (pintype "bidirectional"))
      (node (ref "B1") (pin "32") (pinfunction "32.VDD_32") (pintype "bidirectional"))
      (node (ref "B1") (pin "33") (pinfunction "33.VDD_33") (pintype "bidirectional"))
      (node (ref "B1") (pin "34") (pinfunction "34.VDD_34") (pintype "bidirectional"))
      (node (ref "B1") (pin "35") (pinfunction "35.VDD_35") (pintype "bidirectional"))
      (node (ref "B1") (pin "36") (pinfunction "36.VDD_36") (pintype "bidirectional"))
      (node (ref "B1") (pin "37") (pinfunction "37.VDD_37") (pintype "bidirectional"))
      (node (ref "B1") (pin "38") (pinfunction "38.VDD_38") (pintype "bidirectional"))
      (node (ref "B1") (pin "39") (pinfunction "39.VDD_39") (pintype "bidirectional"))
      (node (ref "B1") (pin "40") (pinfunction "40.VDD_40") (pintype "bidirectional"))
      (node (ref "B1") (pin "41") (pinfunction "41.VDD_41") (pintype "bidirectional"))
      (node (ref "B1") (pin "42") (pinfunction "42.VDD_42") (pintype "bidirectional"))
      (node (ref "B1") (pin "43") (pinfunction "43.VDD_43") (pintype "power_in"))
      (node (ref "B1") (pin "44") (pinfunction "44.VDD_44") (pintype "power_in"))
      (node (ref "B1") (pin "45") (pinfunction "45.VDD_45") (pintype "bidirectional"))
      (node (ref "B1") (pin "46") (pinfunction "46.VDD_46") (pintype "bidirectional"))
      (node (ref "B1") (pin "47") (pinfunction "47.VDD_47") (pintype "bidirectional"))
      (node (ref "B1") (pin "48") (pinfunction "48.VDD_48") (pintype "bidirectional"))
      (node (ref "B2") (pin "13") (pinfunction "13.IOREF_13") (pintype "bidirectional"))
      (node (ref "B2") (pin "14") (pinfunction "14.VDD_14") (pintype "bidirectional"))
      (node (ref "B2") (pin "15") (pinfunction "15.VDD_15") (pintype "bidirectional"))
      (node (ref "B2") (pin "16") (pinfunction "16.VDD_16") (pintype "bidirectional"))
      (node (ref "B2") (pin "17") (pinfunction "17.VDD_17") (pintype "power_in"))
      (node (ref "B2") (pin "18") (pinfunction "18.VDD_18") (pintype "power_in"))
      (node (ref "B2") (pin "19") (pinfunction "19.VDD_19") (pintype "power_in"))
      (node (ref "B2") (pin "20") (pinfunction "20.VDD_20") (pintype "bidirectional"))
      (node (ref "B2") (pin "21") (pinfunction "21.VDD_21") (pintype "bidirectional"))
      (node (ref "B2") (pin "22") (pinfunction "22.VDD_22") (pintype "bidirectional"))
      (node (ref "B2") (pin "23") (pinfunction "23.VDD_23") (pintype "bidirectional"))
      (node (ref "B2") (pin "24") (pinfunction "24.VDD_24") (pintype "bidirectional"))
      (node (ref "B2") (pin "25") (pinfunction "25.VDD_25") (pintype "bidirectional"))
      (node (ref "B2") (pin "26") (pinfunction "26.VDD_26") (pintype "bidirectional"))
      (node (ref "B2") (pin "27") (pinfunction "27.VDD_27") (pintype "bidirectional"))
      (node (ref "B2") (pin "28") (pinfunction "28.VDD_28") (pintype "bidirectional"))
      (node (ref "B2") (pin "29") (pinfunction "29.VDD_29") (pintype "bidirectional"))
      (node (ref "B2") (pin "30") (pinfunction "30.VDD_30") (pintype "bidirectional"))
      (node (ref "B2") (pin "31") (pinfunction "31.VDD_31") (pintype "bidirectional"))
      (node (ref "B2") (pin "32") (pinfunction "32.VDD_32") (pintype "bidirectional"))
      (node (ref "B2") (pin "33") (pinfunction "33.VDD_33") (pintype "bidirectional"))
      (node (ref "B2") (pin "34") (pinfunction "34.VDD_34") (pintype "bidirectional"))
      (node (ref "B2") (pin "35") (pinfunction "35.VDD_35") (pintype "bidirectional"))
      (node (ref "B2") (pin "36") (pinfunction "36.VDD_36") (pintype "bidirectional"))
      (node (ref "B2") (pin "37") (pinfunction "37.VDD_37") (pintype "bidirectional"))
      (node (ref "B2") (pin "38") (pinfunction "38.VDD_38") (pintype "bidirectional"))
      (node (ref "B2") (pin "39") (pinfunction "39.VDD_39") (pintype "bidirectional"))
      (node (ref "B2") (pin "40") (pinfunction "40.VDD_40") (pintype "bidirectional"))
      (node (ref "B2") (pin "41") (pinfunction "41.VDD_41") (pintype "bidirectional"))
      (node (ref "B2") (pin "42") (pinfunction "42.VDD_42") (pintype "bidirectional"))
      (node (ref "B2") (pin "43") (pinfunction "43.VDD_43") (pintype "power_in"))
      (node (ref "B2") (pin "44") (pinfunction "44.VDD_44") (pintype "power_in"))
      (node (ref "B2") (pin "45") (pinfunction "45.VDD_45") (pintype "bidirectional"))
      (node (ref "B2") (pin "46") (pinfunction "46.VDD_46") (pintype "bidirectional"))
      (node (ref "B2") (pin "47") (pinfunction "47.VDD_47") (pintype "bidirectional"))
      (node (ref "B2") (pin "48") (pinfunction "48.VDD_48") (pintype "bidirectional"))
      (node (ref "B3") (pin "13") (pinfunction "13.IOREF_13") (pintype "bidirectional"))
      (node (ref "B3") (pin "14") (pinfunction "14.VDD_14") (pintype "bidirectional"))
      (node (ref "B3") (pin "15") (pinfunction "15.VDD_15") (pintype "bidirectional"))
      (node (ref "B3") (pin "16") (pinfunction "16.VDD_16") (pintype "bidirectional"))
      (node (ref "B3") (pin "17") (pinfunction "17.VDD_17") (pintype "power_in"))
      (node (ref "B3") (pin "18") (pinfunction "18.VDD_18") (pintype "power_in"))
      (node (ref "B3") (pin "19") (pinfunction "19.VDD_19") (pintype "power_in"))
      (node (ref "B3") (pin "20") (pinfunction "20.VDD_20") (pintype "bidirectional"))
      (node (ref "B3") (pin "21") (pinfunction "21.VDD_21") (pintype "bidirectional"))
      (node (ref "B3") (pin "22") (pinfunction "22.VDD_22") (pintype "bidirectional"))
      (node (ref "B3") (pin "23") (pinfunction "23.VDD_23") (pintype "bidirectional"))
      (node (ref "B3") (pin "24") (pinfunction "24.VDD_24") (pintype "bidirectional"))
      (node (ref "B3") (pin "25") (pinfunction "25.VDD_25") (pintype "bidirectional"))
      (node (ref "B3") (pin "26") (pinfunction "26.VDD_26") (pintype "bidirectional"))
      (node (ref "B3") (pin "27") (pinfunction "27.VDD_27") (pintype "bidirectional"))
      (node (ref "B3") (pin "28") (pinfunction "28.VDD_28") (pintype "bidirectional"))
      (node (ref "B3") (pin "29") (pinfunction "29.VDD_29") (pintype "bidirectional"))
      (node (ref "B3") (pin "30") (pinfunction "30.VDD_30") (pintype "bidirectional"))
      (node (ref "B3") (pin "31") (pinfunction "31.VDD_31") (pintype "bidirectional"))
      (node (ref "B3") (pin "32") (pinfunction "32.VDD_32") (pintype "bidirectional"))
      (node (ref "B3") (pin "33") (pinfunction "33.VDD_33") (pintype "bidirectional"))
      (node (ref "B3") (pin "34") (pinfunction "34.VDD_34") (pintype "bidirectional"))
      (node (ref "B3") (pin "35") (pinfunction "35.VDD_35") (pintype "bidirectional"))
      (node (ref "B3") (pin "36") (pinfunction "36.VDD_36") (pintype "bidirectional"))
      (node (ref "B3") (pin "37") (pinfunction "37.VDD_37") (pintype "bidirectional"))
      (node (ref "B3") (pin "38") (pinfunction "38.VDD_38") (pintype "bidirectional"))
      (node (ref "B3") (pin "39") (pinfunction "39.VDD_39") (pintype "bidirectional"))
      (node (ref "B3") (pin "40") (pinfunction "40.VDD_40") (pintype "bidirectional"))
      (node (ref "B3") (pin "41") (pinfunction "41.VDD_41") (pintype "bidirectional"))
      (node (ref "B3") (pin "42") (pinfunction "42.VDD_42") (pintype "bidirectional"))
      (node (ref "B3") (pin "43") (pinfunction "43.VDD_43") (pintype "power_in"))
      (node (ref "B3") (pin "44") (pinfunction "44.VDD_44") (pintype "power_in"))
      (node (ref "B3") (pin "45") (pinfunction "45.VDD_45") (pintype "bidirectional"))
      (node (ref "B3") (pin "46") (pinfunction "46.VDD_46") (pintype "bidirectional"))
      (node (ref "B3") (pin "47") (pinfunction "47.VDD_47") (pintype "bidirectional"))
      (node (ref "B3") (pin "48") (pinfunction "48.VDD_48") (pintype "bidirectional"))
      (node (ref "B4") (pin "13") (pinfunction "13.IOREF_13") (pintype "bidirectional"))
      (node (ref "B4") (pin "14") (pinfunction "14.VDD_14") (pintype "bidirectional"))
      (node (ref "B4") (pin "15") (pinfunction "15.VDD_15") (pintype "bidirectional"))
      (node (ref "B4") (pin "16") (pinfunction "16.VDD_16") (pintype "bidirectional"))
      (node (ref "B4") (pin "17") (pinfunction "17.VDD_17") (pintype "power_in"))
      (node (ref "B4") (pin "18") (pinfunction "18.VDD_18") (pintype "power_in"))
      (node (ref "B4") (pin "19") (pinfunction "19.VDD_19") (pintype "power_in"))
      (node (ref "B4") (pin "20") (pinfunction "20.VDD_20") (pintype "bidirectional"))
      (node (ref "B4") (pin "21") (pinfunction "21.VDD_21") (pintype "bidirectional"))
      (node (ref "B4") (pin "22") (pinfunction "22.VDD_22") (pintype "bidirectional"))
      (node (ref "B4") (pin "23") (pinfunction "23.VDD_23") (pintype "bidirectional"))
      (node (ref "B4") (pin "24") (pinfunction "24.VDD_24") (pintype "bidirectional"))
      (node (ref "B4") (pin "25") (pinfunction "25.VDD_25") (pintype "bidirectional"))
      (node (ref "B4") (pin "26") (pinfunction "26.VDD_26") (pintype "bidirectional"))
      (node (ref "B4") (pin "27") (pinfunction "27.VDD_27") (pintype "bidirectional"))
      (node (ref "B4") (pin "28") (pinfunction "28.VDD_28") (pintype "bidirectional"))
      (node (ref "B4") (pin "29") (pinfunction "29.VDD_29") (pintype "bidirectional"))
      (node (ref "B4") (pin "30") (pinfunction "30.VDD_30") (pintype "bidirectional"))
      (node (ref "B4") (pin "31") (pinfunction "31.VDD_31") (pintype "bidirectional"))
      (node (ref "B4") (pin "32") (pinfunction "32.VDD_32") (pintype "bidirectional"))
      (node (ref "B4") (pin "33") (pinfunction "33.VDD_33") (pintype "bidirectional"))
      (node (ref "B4") (pin "34") (pinfunction "34.VDD_34") (pintype "bidirectional"))
      (node (ref "B4") (pin "35") (pinfunction "35.VDD_35") (pintype "bidirectional"))
      (node (ref "B4") (pin "36") (pinfunction "36.VDD_36") (pintype "bidirectional"))
      (node (ref "B4") (pin "37") (pinfunction "37.VDD_37") (pintype "bidirectional"))
      (node (ref "B4") (pin "38") (pinfunction "38.VDD_38") (pintype "bidirectional"))
      (node (ref "B4") (pin "39") (pinfunction "39.VDD_39") (pintype "bidirectional"))
      (node (ref "B4") (pin "40") (pinfunction "40.VDD_40") (pintype "bidirectional"))
      (node (ref "B4") (pin "41") (pinfunction "41.VDD_41") (pintype "bidirectional"))
      (node (ref "B4") (pin "42") (pinfunction "42.VDD_42") (pintype "bidirectional"))
      (node (ref "B4") (pin "43") (pinfunction "43.VDD_43") (pintype "power_in"))
      (node (ref "B4") (pin "44") (pinfunction "44.VDD_44") (pintype "power_in"))
      (node (ref "B4") (pin "45") (pinfunction "45.VDD_45") (pintype "bidirectional"))
      (node (ref "B4") (pin "46") (pinfunction "46.VDD_46") (pintype "bidirectional"))
      (node (ref "B4") (pin "47") (pinfunction "47.VDD_47") (pintype "bidirectional"))
      (node (ref "B4") (pin "48") (pinfunction "48.VDD_48") (pintype "bidirectional"))
      (node (ref "B5") (pin "13") (pinfunction "13.IOREF_13") (pintype "bidirectional"))
      (node (ref "B5") (pin "14") (pinfunction "14.VDD_14") (pintype "bidirectional"))
      (node (ref "B5") (pin "15") (pinfunction "15.VDD_15") (pintype "bidirectional"))
      (node (ref "B5") (pin "16") (pinfunction "16.VDD_16") (pintype "bidirectional"))
      (node (ref "B5") (pin "17") (pinfunction "17.VDD_17") (pintype "power_in"))
      (node (ref "B5") (pin "18") (pinfunction "18.VDD_18") (pintype "power_in"))
      (node (ref "B5") (pin "19") (pinfunction "19.VDD_19") (pintype "power_in"))
      (node (ref "B5") (pin "20") (pinfunction "20.VDD_20") (pintype "bidirectional"))
      (node (ref "B5") (pin "21") (pinfunction "21.VDD_21") (pintype "bidirectional"))
      (node (ref "B5") (pin "22") (pinfunction "22.VDD_22") (pintype "bidirectional"))
      (node (ref "B5") (pin "23") (pinfunction "23.VDD_23") (pintype "bidirectional"))
      (node (ref "B5") (pin "24") (pinfunction "24.VDD_24") (pintype "bidirectional"))
      (node (ref "B5") (pin "25") (pinfunction "25.VDD_25") (pintype "bidirectional"))
      (node (ref "B5") (pin "26") (pinfunction "26.VDD_26") (pintype "bidirectional"))
      (node (ref "B5") (pin "27") (pinfunction "27.VDD_27") (pintype "bidirectional"))
      (node (ref "B5") (pin "28") (pinfunction "28.VDD_28") (pintype "bidirectional"))
      (node (ref "B5") (pin "29") (pinfunction "29.VDD_29") (pintype "bidirectional"))
      (node (ref "B5") (pin "30") (pinfunction "30.VDD_30") (pintype "bidirectional"))
      (node (ref "B5") (pin "31") (pinfunction "31.VDD_31") (pintype "bidirectional"))
      (node (ref "B5") (pin "32") (pinfunction "32.VDD_32") (pintype "bidirectional"))
      (node (ref "B5") (pin "33") (pinfunction "33.VDD_33") (pintype "bidirectional"))
      (node (ref "B5") (pin "34") (pinfunction "34.VDD_34") (pintype "bidirectional"))
      (node (ref "B5") (pin "35") (pinfunction "35.VDD_35") (pintype "bidirectional"))
      (node (ref "B5") (pin "36") (pinfunction "36.VDD_36") (pintype "bidirectional"))
      (node (ref "B5") (pin "37") (pinfunction "37.VDD_37") (pintype "bidirectional"))
      (node (ref "B5") (pin "38") (pinfunction "38.VDD_38") (pintype "bidirectional"))
      (node (ref "B5") (pin "39") (pinfunction "39.VDD_39") (pintype "bidirectional"))
      (node (ref "B5") (pin "40") (pinfunction "40.VDD_40") (pintype "bidirectional"))
      (node (ref "B5") (pin "41") (pinfunction "41.VDD_41") (pintype "bidirectional"))
      (node (ref "B5") (pin "42") (pinfunction "42.VDD_42") (pintype "bidirectional"))
      (node (ref "B5") (pin "43") (pinfunction "43.VDD_43") (pintype "power_in"))
      (node (ref "B5") (pin "44") (pinfunction "44.VDD_44") (pintype "power_in"))
      (node (ref "B5") (pin "45") (pinfunction "45.VDD_45") (pintype "bidirectional"))
      (node (ref "B5") (pin "46") (pinfunction "46.VDD_46") (pintype "bidirectional"))
      (node (ref "B5") (pin "47") (pinfunction "47.VDD_47") (pintype "bidirectional"))
      (node (ref "B5") (pin "48") (pinfunction "48.VDD_48") (pintype "bidirectional"))
      (node (ref "C11") (pin "+") (pinfunction "+_+") (pintype "passive"))
      (node (ref "C12") (pin "1") (pinfunction "1_1") (pintype "passive"))
      (node (ref "C16") (pin "1") (pinfunction "1_1") (pintype "passive"))
      (node (ref "C2") (pin "2") (pinfunction "2_2") (pintype "passive"))
      (node (ref "C3") (pin "2") (pinfunction "2_2") (pintype "passive"))
      (node (ref "C4") (pin "2") (pinfunction "2_2") (pintype "passive"))
      (node (ref "C5") (pin "2") (pinfunction "2_2") (pintype "passive"))
      (node (ref "C6") (pin "2") (pinfunction "2_2") (pintype "passive"))
      (node (ref "C7") (pin "2") (pinfunction "2_2") (pintype "passive"))
      (node (ref "C9") (pin "+") (pinfunction "+_+") (pintype "passive"))
      (node (ref "U$5") (pin "1") (pinfunction "VOUT_1") (pintype "passive"))
      (node (ref "U$5") (pin "7") (pinfunction "+SENSE_7") (pintype "passive"))
    )
    (net (code "32") (name "VCC_1V8") (class "Default")
      (node (ref "1V8") (pin "TP") (pinfunction "TP_TP") (pintype "input"))
      (node (ref "C15") (pin "1") (pinfunction "1_1") (pintype "passive"))
      (node (ref "C19") (pin "1") (pinfunction "1_1") (pintype "passive"))
      (node (ref "C8") (pin "1") (pinfunction "1_1") (pintype "passive"))
      (node (ref "R1") (pin "2") (pinfunction "2_2") (pintype "passive"))
      (node (ref "R2") (pin "2") (pinfunction "2_2") (pintype "passive"))
      (node (ref "R3") (pin "2") (pinfunction "2_2") (pintype "passive"))
      (node (ref "R4") (pin "2") (pinfunction "2_2") (pintype "passive"))
      (node (ref "R5") (pin "2") (pinfunction "2_2") (pintype "passive"))
      (node (ref "RG02") (pin "2") (pinfunction "2.OUT_2") (pintype "passive"))
      (node (ref "U10B1") (pin "1") (pinfunction "1.VCC1_1") (pintype "passive"))
    )
    (net (code "33") (name "VCC_3V3") (class "Default")
      (node (ref "3V3") (pin "TP") (pinfunction "TP_TP") (pintype "input"))
      (node (ref "C18") (pin "1") (pinfunction "1_1") (pintype "passive"))
      (node (ref "IN1") (pin "5") (pinfunction "5_5") (pintype "passive"))
      (node (ref "OUT1") (pin "1") (pinfunction "1_1") (pintype "passive"))
      (node (ref "RG02") (pin "1") (pinfunction "1.IN_1") (pintype "passive"))
      (node (ref "U10B1") (pin "5") (pinfunction "5.VCC_5") (pintype "passive"))
    )
    (net (code "34") (name "unconnected-(B1-5.OUTCLK-Pad5)") (class "Default")
      (node (ref "B1") (pin "5") (pinfunction "5.OUTCLK_5") (pintype "bidirectional"))
    )
    (net (code "35") (name "unconnected-(B2-5.OUTCLK-Pad5)") (class "Default")
      (node (ref "B2") (pin "5") (pinfunction "5.OUTCLK_5") (pintype "bidirectional"))
    )
    (net (code "36") (name "unconnected-(B3-5.OUTCLK-Pad5)") (class "Default")
      (node (ref "B3") (pin "5") (pinfunction "5.OUTCLK_5") (pintype "bidirectional"))
    )
    (net (code "37") (name "unconnected-(B4-5.OUTCLK-Pad5)") (class "Default")
      (node (ref "B4") (pin "5") (pinfunction "5.OUTCLK_5") (pintype "bidirectional"))
    )
    (net (code "38") (name "unconnected-(B5-5.OUTCLK-Pad5)") (class "Default")
      (node (ref "B5") (pin "5") (pinfunction "5.OUTCLK_5") (pintype "bidirectional"))
    )
    (net (code "39") (name "unconnected-(U$5-ENABLE-Pad5)") (class "Default")
      (node (ref "U$5") (pin "5") (pinfunction "ENABLE_5") (pintype "passive"))
    )
    (net (code "40") (name "unconnected-(U$5-PG-Pad4)") (class "Default")
      (node (ref "U$5") (pin "4") (pinfunction "PG_4") (pintype "passive"))
    )
  )
)
